# USB_and_POWER.net
KiCad netlist of a schematic drawn in Altium Designer
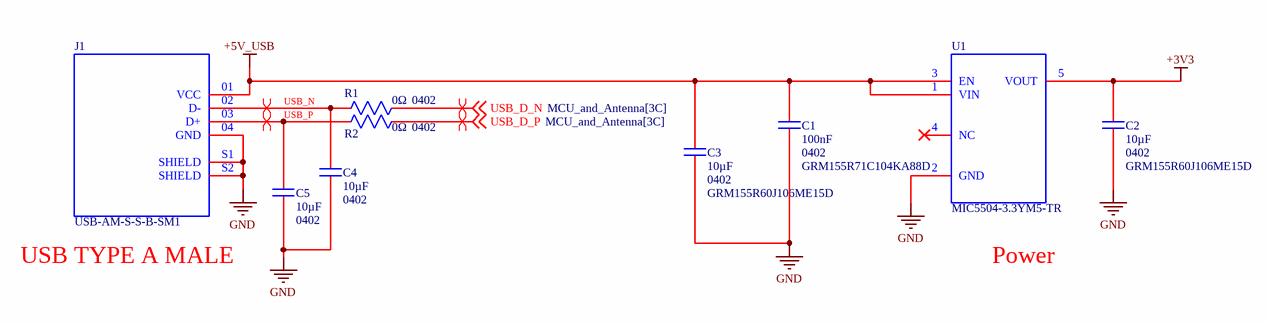
[diagram p0: USB_and_POWER.SchDoc]

(export (version "E")
  (design (tool "Eeschema 10.0.6"))
  (components
    (comp (ref "C1")
      (value "GRM155R71C104KA88D")
      (footprint "CAPC1005X55N")
      (description "16V 100nF X7R ±10% 0402 Multilayer Ceramic Capacitors MLCC - SMD/SMT ROHS")
      (fields
        (field (name "MANUFACTURER") "Murata")
        (field (name "TOLERANCE") "10%")
        (field (name "CASE/PACKAGE") "0402")
        (field (name "ALTIUM_VALUE") "100nF")
      )
      (libsource (lib "Schlib") (part "GRM155R71C104KA88D"))
    )
    (comp (ref "C2")
      (value "GRM155R60J106ME15D")
      (footprint "CAPC1005X55N")
      (description "6.3V 10uF X5R ±20% 0402 Multilayer Ceramic Capacitors MLCC - SMD/SMT ROHS")
      (fields
        (field (name "MANUFACTURER") "Murata")
        (field (name "TOLERANCE") "20%")
        (field (name "CASE/PACKAGE") "0402")
        (field (name "ALTIUM_VALUE") "10µF")
      )
      (libsource (lib "Schlib") (part "GRM155R60J106ME15D"))
    )
    (comp (ref "C3")
      (value "GRM155R60J106ME15D")
      (footprint "CAPC1005X55N")
      (description "6.3V 10uF X5R ±20% 0402 Multilayer Ceramic Capacitors MLCC - SMD/SMT ROHS")
      (fields
        (field (name "MANUFACTURER") "Murata")
        (field (name "TOLERANCE") "20%")
        (field (name "CASE/PACKAGE") "0402")
        (field (name "ALTIUM_VALUE") "10µF")
      )
      (libsource (lib "Schlib") (part "GRM155R60J106ME15D"))
    )
    (comp (ref "C4")
      (value "10µF")
      (footprint "CAPC1005X55N")
      (description "6.3V 10uF X5R ±20% 0402 Multilayer Ceramic Capacitors MLCC - SMD/SMT ROHS")
      (fields
        (field (name "MANUFACTURER") "Murata")
        (field (name "MANUFACTURER PART NUMBER") "GRM155R60J106ME15D")
        (field (name "CASE/PACKAGE") "0402")
      )
      (libsource (lib "Schlib") (part "GRM155R60J106ME15D"))
    )
    (comp (ref "C5")
      (value "10µF")
      (footprint "CAPC1005X55N")
      (description "6.3V 10uF X5R ±20% 0402 Multilayer Ceramic Capacitors MLCC - SMD/SMT ROHS")
      (fields
        (field (name "MANUFACTURER") "Murata")
        (field (name "MANUFACTURER PART NUMBER") "GRM155R60J106ME15D")
        (field (name "CASE/PACKAGE") "0402")
      )
      (libsource (lib "Schlib") (part "GRM155R60J106ME15D"))
    )
    (comp (ref "J1")
      (value "USB-AM-S-S-B-SM1")
      (footprint "SAMTEC_USB-AM-S-X-X-SM1")
      (description "USB Connector, USB Type A, USB 2.0, Plug, 4 Positions, Surface Mount, Right Angle")
      (fields (field (name "MANUFACTURER") "Samtec") (field (name "LCSC PART") "C7374540"))
      (libsource (lib "Schlib") (part "USB-AM-S-S-B-SM1"))
    )
    (comp (ref "R1")
      (value "0Ω")
      (footprint "RC0402N_YAG-M")
      (description "GENERAL PURPOSE CHIP RESISTOR Metal Glaze/thick Film, 0.0625W, 0ohm, Surface Mount, 0402")
      (fields
        (field (name "MANUFACTURER") "Yageo Group")
        (field (name "MANUFACTURER PART NUMBER") "RC0402JR-070RL")
        (field (name "CASE/PACKAGE") "0402")
      )
      (libsource (lib "Schlib") (part "RC0402JR-070RL"))
    )
    (comp (ref "R2")
      (value "0Ω")
      (footprint "RC0402N_YAG-M")
      (description "GENERAL PURPOSE CHIP RESISTOR Metal Glaze/thick Film, 0.0625W, 0ohm, Surface Mount, 0402")
      (fields
        (field (name "MANUFACTURER") "Yageo Group")
        (field (name "MANUFACTURER PART NUMBER") "RC0402JR-070RL")
        (field (name "CASE/PACKAGE") "0402")
      )
      (libsource (lib "Schlib") (part "RC0402JR-070RL"))
    )
    (comp (ref "U1")
      (value "MIC5504-3.3YM5-TR")
      (footprint "SOT-23-5_MC_MCH")
      (description "MIC5504 Series 3.3 V 300 mA Surface Mount Fixed Single Output LDO - SOT-23-5")
      (fields (field (name "MANUFACTURER") "Microchip") (field (name "LCSC PART") "C88419"))
      (libsource (lib "Schlib") (part "MIC5504-3.3YM5-TR"))
    )
  )
  (nets
    (net (code "1") (name "+3V3") (class "Default")
      (node (ref "C2") (pin "2") (pinfunction "2_2") (pintype "passive"))
      (node (ref "U1") (pin "5") (pinfunction "VOUT_5") (pintype "passive"))
    )
    (net (code "2") (name "+5V_USB") (class "Default")
      (node (ref "C1") (pin "2") (pinfunction "2_2") (pintype "passive"))
      (node (ref "C3") (pin "2") (pinfunction "2_2") (pintype "passive"))
      (node (ref "J1") (pin "01") (pinfunction "VCC_01") (pintype "passive"))
      (node (ref "U1") (pin "1") (pinfunction "VIN_1") (pintype "passive"))
      (node (ref "U1") (pin "3") (pinfunction "EN_3") (pintype "passive"))
    )
    (net (code "3") (name "/USB_N") (class "Default")
      (node (ref "C4") (pin "2") (pinfunction "2_2") (pintype "passive"))
      (node (ref "J1") (pin "02") (pinfunction "D-_02") (pintype "passive"))
      (node (ref "R1") (pin "1") (pinfunction "1_1") (pintype "passive"))
    )
    (net (code "4") (name "/USB_P") (class "Default")
      (node (ref "C5") (pin "2") (pinfunction "2_2") (pintype "passive"))
      (node (ref "J1") (pin "03") (pinfunction "D+_03") (pintype "passive"))
      (node (ref "R2") (pin "1") (pinfunction "1_1") (pintype "passive"))
    )
    (net (code "5") (name "GND") (class "Default")
      (node (ref "C1") (pin "1") (pinfunction "1_1") (pintype "passive"))
      (node (ref "C2") (pin "1") (pinfunction "1_1") (pintype "passive"))
      (node (ref "C3") (pin "1") (pinfunction "1_1") (pintype "passive"))
      (node (ref "C4") (pin "1") (pinfunction "1_1") (pintype "passive"))
      (node (ref "C5") (pin "1") (pinfunction "1_1") (pintype "passive"))
      (node (ref "J1") (pin "04") (pinfunction "GND_04") (pintype "passive"))
      (node (ref "J1") (pin "S1") (pinfunction "SHIELD_S1") (pintype "passive"))
      (node (ref "J1") (pin "S2") (pinfunction "SHIELD_S2") (pintype "passive"))
      (node (ref "U1") (pin "2") (pinfunction "GND_2") (pintype "passive"))
    )
    (net (code "6") (name "USB_D_N") (class "Default")
      (node (ref "R1") (pin "2") (pinfunction "2_2") (pintype "passive"))
    )
    (net (code "7") (name "USB_D_P") (class "Default")
      (node (ref "R2") (pin "2") (pinfunction "2_2") (pintype "passive"))
    )
    (net (code "8") (name "unconnected-(U1-NC-Pad4)") (class "Default")
      (node (ref "U1") (pin "4") (pinfunction "NC_4") (pintype "passive+no_connect"))
    )
  )
)
